# testv3.net
KiCad netlist of a schematic drawn in EAGLE
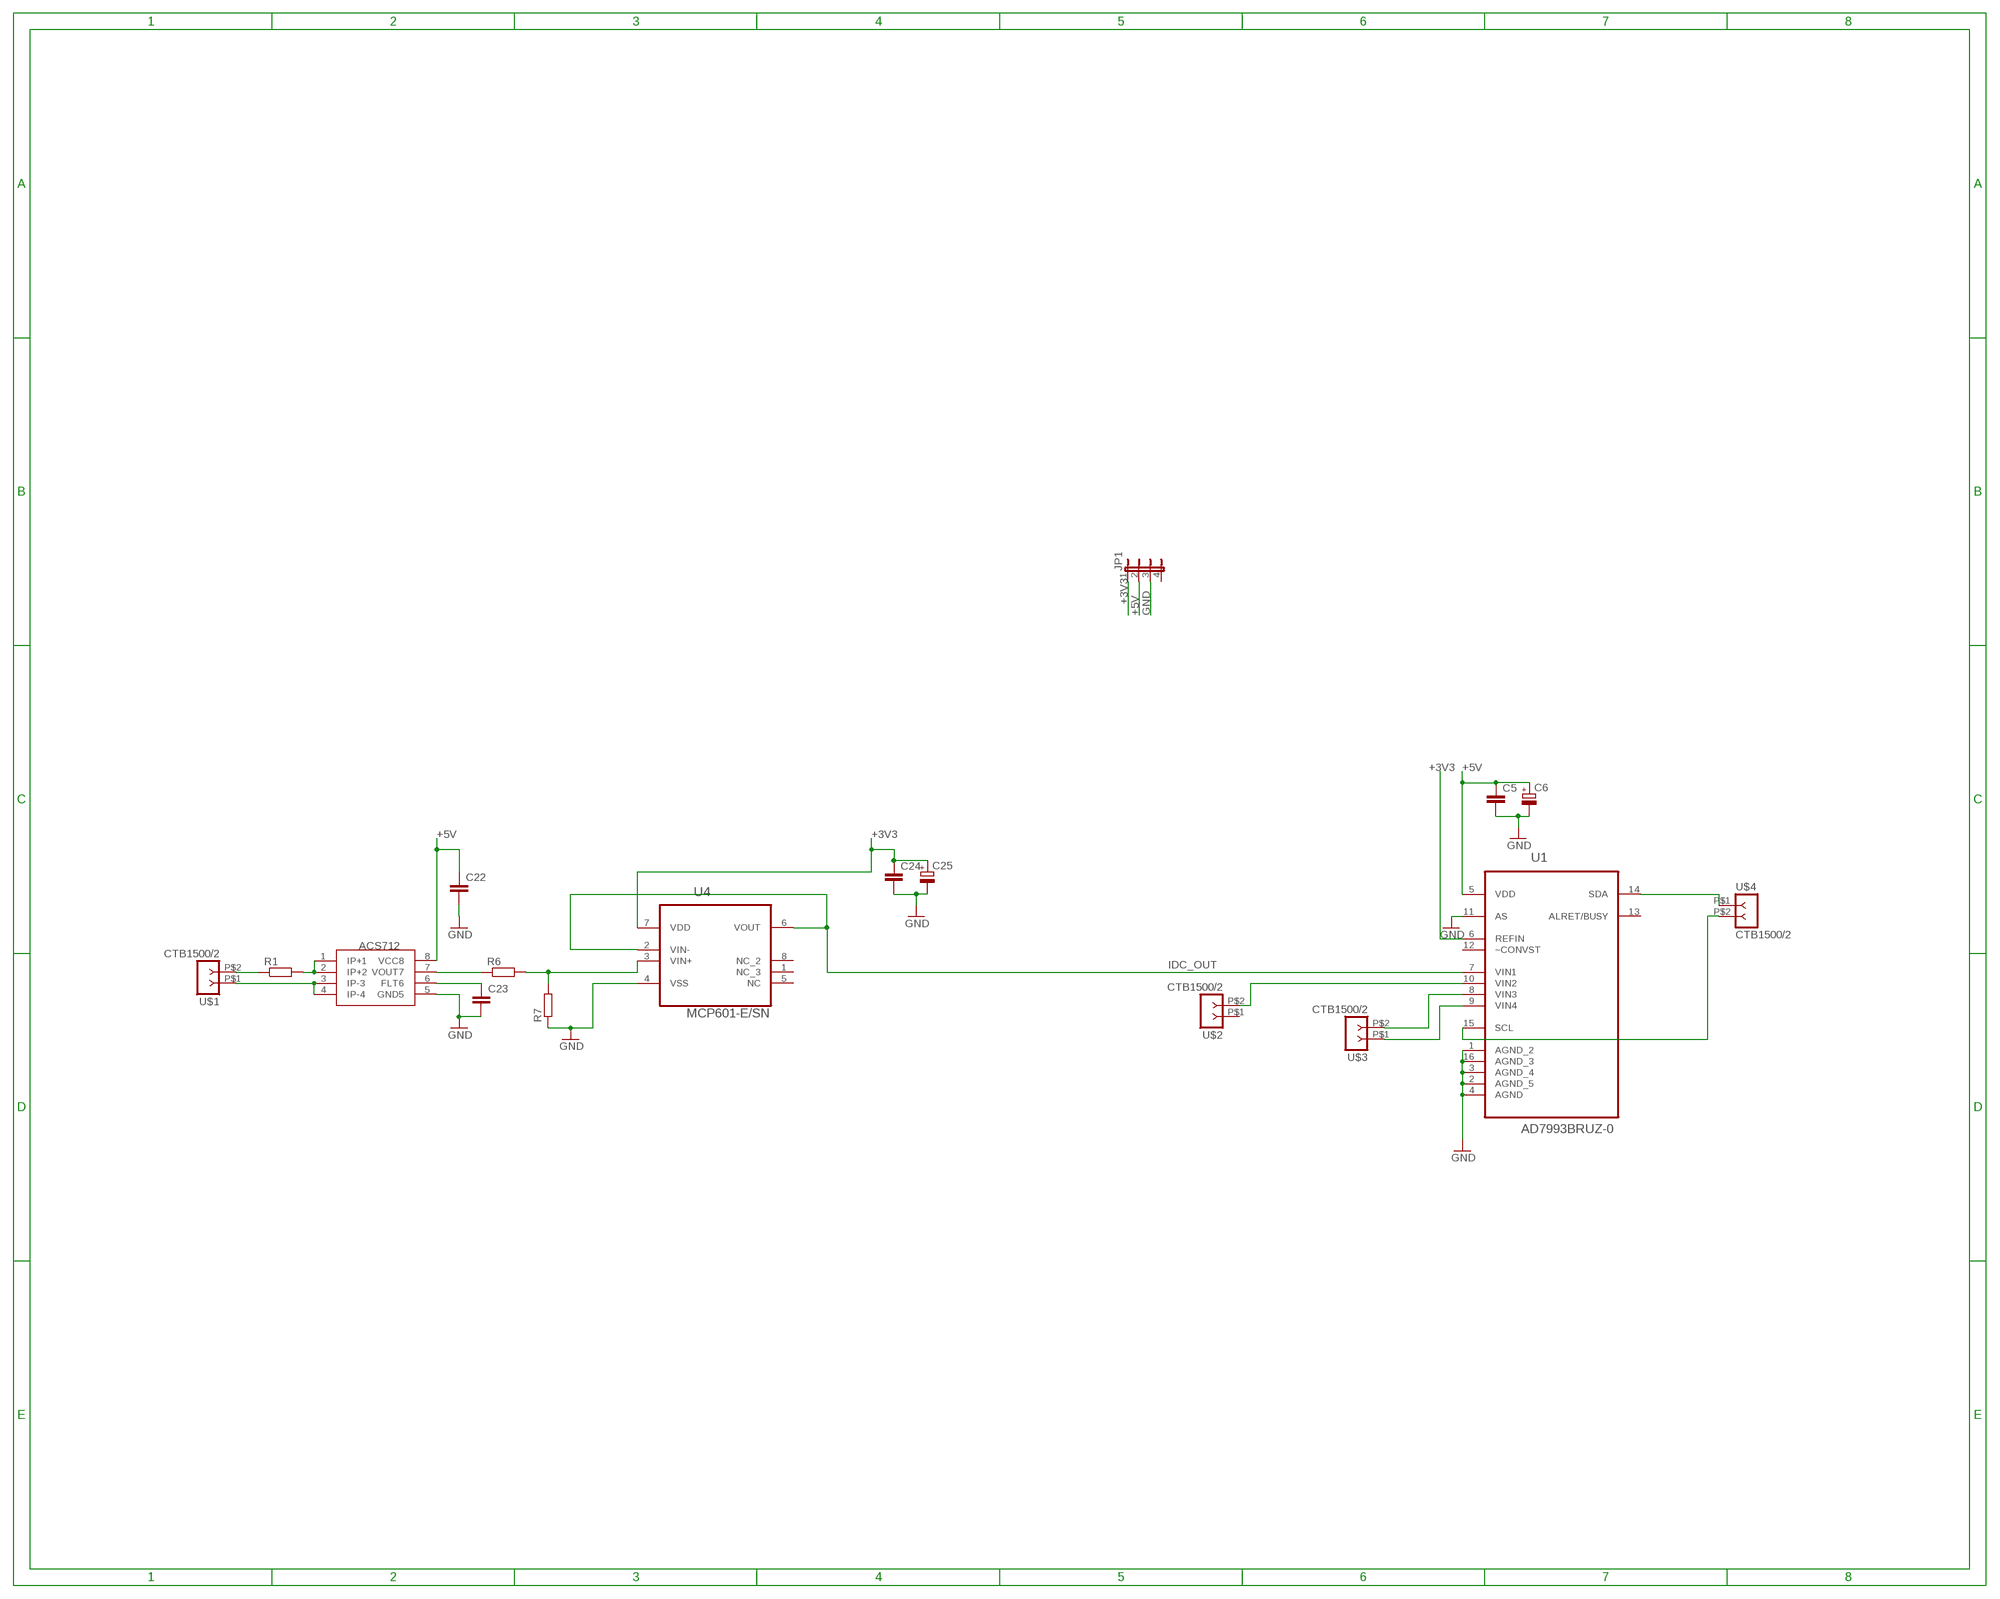
[diagram p0: schematic, sheet 1]

(export (version "E")
  (design (tool "Eeschema 10.0.6"))
  (components
    (comp (ref "C5")
      (value "C-EU025-025X050")
      (footprint "eagle-import:C025-025X050")
      (libsource (lib "eagle-import") (part "C-EU025-025X050"))
    )
    (comp (ref "C6")
      (value "CPOL-EUE2-4")
      (footprint "eagle-import:E2-4")
      (libsource (lib "eagle-import") (part "CPOL-EUE2-4"))
    )
    (comp (ref "C22")
      (value "C-EU025-025X050")
      (footprint "eagle-import:C025-025X050")
      (libsource (lib "eagle-import") (part "C-EU025-025X050"))
    )
    (comp (ref "C23")
      (value "C-EU025-025X050")
      (footprint "eagle-import:C025-025X050")
      (libsource (lib "eagle-import") (part "C-EU025-025X050"))
    )
    (comp (ref "C24")
      (value "C-EU025-025X050")
      (footprint "eagle-import:C025-025X050")
      (libsource (lib "eagle-import") (part "C-EU025-025X050"))
    )
    (comp (ref "C25")
      (value "CPOL-EUE2-4")
      (footprint "eagle-import:E2-4")
      (libsource (lib "eagle-import") (part "CPOL-EUE2-4"))
    )
    (comp (ref "JP1")
      (value "JP4E")
      (footprint "eagle-import:JP4")
      (libsource (lib "eagle-import") (part "JP4E"))
    )
    (comp (ref "R1")
      (value "R-EU_0207/7")
      (footprint "eagle-import:0207_7")
      (libsource (lib "eagle-import") (part "R-EU_0207/7"))
    )
    (comp (ref "R6")
      (value "R-EU_0207/7")
      (footprint "eagle-import:0207_7")
      (libsource (lib "eagle-import") (part "R-EU_0207/7"))
    )
    (comp (ref "R7")
      (value "R-EU_0207/7")
      (footprint "eagle-import:0207_7")
      (libsource (lib "eagle-import") (part "R-EU_0207/7"))
    )
    (comp (ref "U$1")
      (value "CTB1500/2")
      (footprint "eagle-import:CTB1500-2")
      (libsource (lib "eagle-import") (part "CTB1500/2"))
    )
    (comp (ref "U$2")
      (value "CTB1500/2")
      (footprint "eagle-import:CTB1500-2")
      (libsource (lib "eagle-import") (part "CTB1500/2"))
    )
    (comp (ref "U$3")
      (value "CTB1500/2")
      (footprint "eagle-import:CTB1500-2")
      (libsource (lib "eagle-import") (part "CTB1500/2"))
    )
    (comp (ref "U$4")
      (value "CTB1500/2")
      (footprint "eagle-import:CTB1500-2")
      (libsource (lib "eagle-import") (part "CTB1500/2"))
    )
    (comp (ref "U$10")
      (value "ACS712")
      (footprint "eagle-import:SOIC8")
      (libsource (lib "eagle-import") (part "ACS712"))
    )
    (comp (ref "U1")
      (value "AD7993BRUZ-0")
      (footprint "eagle-import:SOP65P640X120-16N")
      (libsource (lib "eagle-import") (part "AD7993BRUZ-0"))
    )
    (comp (ref "U4")
      (value "MCP601-E/SN")
      (footprint "eagle-import:SOIC127P600X175-8N")
      (libsource (lib "eagle-import") (part "MCP601-E/SN"))
    )
  )
  (nets
    (net (code "1") (name "/+3V3") (class "Default")
      (node (ref "C24") (pin "1") (pinfunction "1_1") (pintype "passive"))
      (node (ref "C25") (pin "+") (pinfunction "+_+") (pintype "passive"))
      (node (ref "JP1") (pin "1") (pinfunction "1_1") (pintype "passive"))
      (node (ref "U1") (pin "6") (pinfunction "REFIN_6") (pintype "input"))
      (node (ref "U4") (pin "7") (pinfunction "VDD_7") (pintype "power_in"))
    )
    (net (code "2") (name "/+5V") (class "Default")
      (node (ref "C22") (pin "1") (pinfunction "1_1") (pintype "passive"))
      (node (ref "C5") (pin "1") (pinfunction "1_1") (pintype "passive"))
      (node (ref "C6") (pin "+") (pinfunction "+_+") (pintype "passive"))
      (node (ref "JP1") (pin "2") (pinfunction "2_2") (pintype "passive"))
      (node (ref "U$10") (pin "8") (pinfunction "VCC8_8") (pintype "power_in"))
      (node (ref "U1") (pin "5") (pinfunction "VDD_5") (pintype "power_in"))
    )
    (net (code "3") (name "/IDC_OUT") (class "Default")
      (node (ref "U1") (pin "7") (pinfunction "VIN1_7") (pintype "input"))
      (node (ref "U4") (pin "2") (pinfunction "VIN-_2") (pintype "input"))
      (node (ref "U4") (pin "6") (pinfunction "VOUT_6") (pintype "output"))
    )
    (net (code "4") (name "GND") (class "Default")
      (node (ref "C22") (pin "2") (pinfunction "2_2") (pintype "passive"))
      (node (ref "C23") (pin "2") (pinfunction "2_2") (pintype "passive"))
      (node (ref "C24") (pin "2") (pinfunction "2_2") (pintype "passive"))
      (node (ref "C25") (pin "-") (pinfunction "-_-") (pintype "passive"))
      (node (ref "C5") (pin "2") (pinfunction "2_2") (pintype "passive"))
      (node (ref "C6") (pin "-") (pinfunction "-_-") (pintype "passive"))
      (node (ref "JP1") (pin "3") (pinfunction "3_3") (pintype "passive"))
      (node (ref "R7") (pin "1") (pinfunction "1_1") (pintype "passive"))
      (node (ref "U$10") (pin "5") (pinfunction "GND5_5") (pintype "power_in"))
      (node (ref "U1") (pin "1") (pinfunction "AGND_2_1") (pintype "passive"))
      (node (ref "U1") (pin "11") (pinfunction "AS_11") (pintype "input"))
      (node (ref "U1") (pin "16") (pinfunction "AGND_3_16") (pintype "passive"))
      (node (ref "U1") (pin "2") (pinfunction "AGND_5_2") (pintype "passive"))
      (node (ref "U1") (pin "3") (pinfunction "AGND_4_3") (pintype "passive"))
      (node (ref "U1") (pin "4") (pinfunction "AGND_4") (pintype "passive"))
      (node (ref "U4") (pin "4") (pinfunction "VSS_4") (pintype "power_in"))
    )
    (net (code "5") (name "Net-(U$1-1)") (class "Default")
      (node (ref "U$1") (pin "P$1") (pinfunction "1_P$1") (pintype "passive"))
      (node (ref "U$10") (pin "3") (pinfunction "IP-3_3") (pintype "bidirectional"))
      (node (ref "U$10") (pin "4") (pinfunction "IP-4_4") (pintype "bidirectional"))
    )
    (net (code "6") (name "Net-(U$1-2)") (class "Default")
      (node (ref "R1") (pin "1") (pinfunction "1_1") (pintype "passive"))
      (node (ref "U$1") (pin "P$2") (pinfunction "2_P$2") (pintype "passive"))
    )
    (net (code "7") (name "Net-(U$2-2)") (class "Default")
      (node (ref "U$2") (pin "P$2") (pinfunction "2_P$2") (pintype "passive"))
      (node (ref "U1") (pin "10") (pinfunction "VIN2_10") (pintype "input"))
    )
    (net (code "8") (name "Net-(U$3-1)") (class "Default")
      (node (ref "U$3") (pin "P$1") (pinfunction "1_P$1") (pintype "passive"))
      (node (ref "U1") (pin "9") (pinfunction "VIN4_9") (pintype "input"))
    )
    (net (code "9") (name "Net-(U$3-2)") (class "Default")
      (node (ref "U$3") (pin "P$2") (pinfunction "2_P$2") (pintype "passive"))
      (node (ref "U1") (pin "8") (pinfunction "VIN3_8") (pintype "input"))
    )
    (net (code "10") (name "Net-(U$4-1)") (class "Default")
      (node (ref "U$4") (pin "P$1") (pinfunction "1_P$1") (pintype "passive"))
      (node (ref "U1") (pin "14") (pinfunction "SDA_14") (pintype "bidirectional"))
    )
    (net (code "11") (name "Net-(U$4-2)") (class "Default")
      (node (ref "U$4") (pin "P$2") (pinfunction "2_P$2") (pintype "passive"))
      (node (ref "U1") (pin "15") (pinfunction "SCL_15") (pintype "input"))
    )
    (net (code "12") (name "Net-(U$10-FLT6)") (class "Default")
      (node (ref "C23") (pin "1") (pinfunction "1_1") (pintype "passive"))
      (node (ref "U$10") (pin "6") (pinfunction "FLT6_6") (pintype "passive"))
    )
    (net (code "13") (name "Net-(U$10-IP+1)") (class "Default")
      (node (ref "R1") (pin "2") (pinfunction "2_2") (pintype "passive"))
      (node (ref "U$10") (pin "1") (pinfunction "IP+1_1") (pintype "bidirectional"))
      (node (ref "U$10") (pin "2") (pinfunction "IP+2_2") (pintype "bidirectional"))
    )
    (net (code "14") (name "Net-(U$10-VOUT7)") (class "Default")
      (node (ref "R6") (pin "1") (pinfunction "1_1") (pintype "passive"))
      (node (ref "U$10") (pin "7") (pinfunction "VOUT7_7") (pintype "output"))
    )
    (net (code "15") (name "Net-(U4-VIN+)") (class "Default")
      (node (ref "R6") (pin "2") (pinfunction "2_2") (pintype "passive"))
      (node (ref "R7") (pin "2") (pinfunction "2_2") (pintype "passive"))
      (node (ref "U4") (pin "3") (pinfunction "VIN+_3") (pintype "input"))
    )
    (net (code "16") (name "unconnected-(JP1-Pad4)") (class "Default")
      (node (ref "JP1") (pin "4") (pinfunction "4_4") (pintype "passive"))
    )
    (net (code "17") (name "unconnected-(U$2-1-PadP$1)") (class "Default")
      (node (ref "U$2") (pin "P$1") (pinfunction "1_P$1") (pintype "passive"))
    )
    (net (code "18") (name "unconnected-(U1-ALRET{slash}BUSY-Pad13)") (class "Default")
      (node (ref "U1") (pin "13") (pinfunction "ALRET/BUSY_13") (pintype "output"))
    )
    (net (code "19") (name "unconnected-(U1-~{CONVST}-Pad12)") (class "Default")
      (node (ref "U1") (pin "12") (pinfunction "~{CONVST}_12") (pintype "input"))
    )
    (net (code "20") (name "unconnected-(U4-NC-Pad5)") (class "Default")
      (node (ref "U4") (pin "5") (pinfunction "NC_5") (pintype "no_connect"))
    )
    (net (code "21") (name "unconnected-(U4-NC_2-Pad8)") (class "Default")
      (node (ref "U4") (pin "8") (pinfunction "NC_2_8") (pintype "no_connect"))
    )
    (net (code "22") (name "unconnected-(U4-NC_3-Pad1)") (class "Default")
      (node (ref "U4") (pin "1") (pinfunction "NC_3_1") (pintype "no_connect"))
    )
  )
)
